# Sheet.net
KiCad netlist of a schematic drawn in Altium Designer
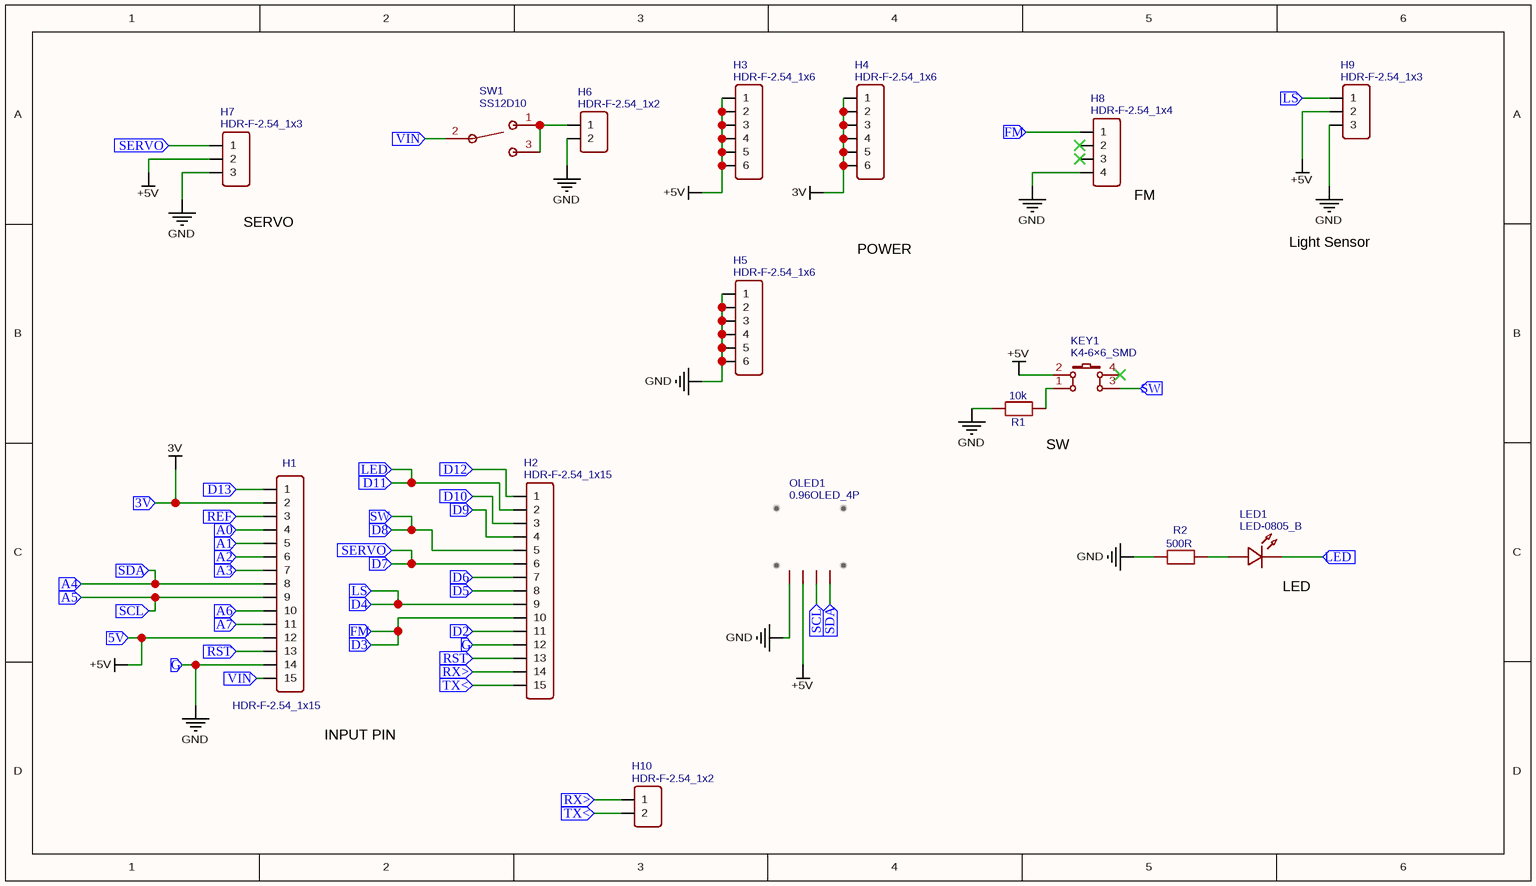
[diagram p0: Sheet.schdoc]

(export (version "E")
  (design (tool "Eeschema 10.0.6"))
  (components
    (comp (ref "H1")
      (value "HDR-F-2.54_1x15")
      (fields (field (name "BOM_SUPPLIER PART") "C124408") (field (name "CONTRIBUTOR") "LCEDA_Lib"))
      (libsource (lib "altium-import") (part "root_0_HDR-F-2.54_1x15_"))
    )
    (comp (ref "H2")
      (value "HDR-F-2.54_1x15")
      (fields (field (name "BOM_SUPPLIER PART") "C124408") (field (name "CONTRIBUTOR") "LCEDA_Lib"))
      (libsource (lib "altium-import") (part "root_0_HDR-F-2.54_1x15_"))
    )
    (comp (ref "H3")
      (value "HDR-F-2.54_1x6")
      (fields (field (name "BOM_SUPPLIER PART") "C40877") (field (name "CONTRIBUTOR") "LCEDA_Lib"))
      (libsource (lib "altium-import") (part "root_0_HDR-F-2.54_1x6_"))
    )
    (comp (ref "H4")
      (value "HDR-F-2.54_1x6")
      (fields (field (name "BOM_SUPPLIER PART") "C40877") (field (name "CONTRIBUTOR") "LCEDA_Lib"))
      (libsource (lib "altium-import") (part "root_0_HDR-F-2.54_1x6_"))
    )
    (comp (ref "H5")
      (value "HDR-F-2.54_1x6")
      (fields (field (name "BOM_SUPPLIER PART") "C40877") (field (name "CONTRIBUTOR") "LCEDA_Lib"))
      (libsource (lib "altium-import") (part "root_0_HDR-F-2.54_1x6_"))
    )
    (comp (ref "H6")
      (value "HDR-F-2.54_1x2")
      (fields (field (name "BOM_SUPPLIER PART") "C49661") (field (name "CONTRIBUTOR") "LCEDA_Lib"))
      (libsource (lib "altium-import") (part "root_0_HDR-F-2.54_1x2_"))
    )
    (comp (ref "H7")
      (value "HDR-F-2.54_1x3")
      (fields (field (name "BOM_SUPPLIER PART") "C146690") (field (name "CONTRIBUTOR") "LCEDA_Lib"))
      (libsource (lib "altium-import") (part "root_0_HDR-F-2.54_1x3_"))
    )
    (comp (ref "H8")
      (value "HDR-F-2.54_1x4")
      (fields (field (name "BOM_SUPPLIER PART") "C225501") (field (name "CONTRIBUTOR") "LCEDA_Lib"))
      (libsource (lib "altium-import") (part "root_0_HDR-F-2.54_1x4_"))
    )
    (comp (ref "H9")
      (value "HDR-F-2.54_1x3")
      (fields (field (name "BOM_SUPPLIER PART") "C146690") (field (name "CONTRIBUTOR") "LCEDA_Lib"))
      (libsource (lib "altium-import") (part "root_0_HDR-F-2.54_1x3_"))
    )
    (comp (ref "H10")
      (value "HDR-F-2.54_1x2")
      (fields (field (name "BOM_SUPPLIER PART") "C49661") (field (name "CONTRIBUTOR") "LCEDA_Lib"))
      (libsource (lib "altium-import") (part "root_0_HDR-F-2.54_1x2_"))
    )
    (comp (ref "KEY1")
      (value "K4-6×6_SMD")
      (fields
        (field (name "BOM_SUPPLIER PART") "C191626")
        (field (name "BOM_MANUFACTURER PART") "K2-6639SP-D4SC-04")
        (field (name "CONTRIBUTOR") "LCEDA_Lib")
      )
      (libsource (lib "altium-import") (part "root_0_K4-6×6_SMD_"))
    )
    (comp (ref "LED1")
      (value "LED-0805_B")
      (fields
        (field (name "BOM_MANUFACTURER PART") "D-B080508B1-KS2")
        (field (name "BOM_SUPPLIER PART") "C108412")
        (field (name "CONTRIBUTOR") "LCEDA_Lib")
      )
      (libsource (lib "altium-import") (part "root_0_LED-0805_B_"))
    )
    (comp (ref "OLED1")
      (value "0.96OLED_4P")
      (fields (field (name "CONTRIBUTOR") "LCEDA_Lib"))
      (libsource (lib "altium-import") (part "root_0_0.96OLED_4P_"))
    )
    (comp (ref "R1")
      (value "10k")
      (fields (field (name "CONTRIBUTOR") "LCEDA_Lib"))
      (libsource (lib "altium-import") (part "root_0_10k_"))
    )
    (comp (ref "R2")
      (value "500R")
      (fields (field (name "CONTRIBUTOR") "LCEDA_Lib"))
      (libsource (lib "altium-import") (part "root_0_500R_"))
    )
    (comp (ref "SW1")
      (value "SS12D10")
      (fields
        (field (name "BOM_SUPPLIER PART") "C273395")
        (field (name "BOM_MANUFACTURER PART") "EG1224")
        (field (name "CONTRIBUTOR") "LCSC")
      )
      (libsource (lib "altium-import") (part "root_0_SS12D10_"))
    )
  )
  (nets
    (net (code "1") (name "+5V") (class "Default")
      (node (ref "H1") (pin "12") (pinfunction "12_12") (pintype "passive"))
      (node (ref "H3") (pin "1") (pinfunction "1_1") (pintype "passive"))
      (node (ref "H3") (pin "2") (pinfunction "2_2") (pintype "passive"))
      (node (ref "H3") (pin "3") (pinfunction "3_3") (pintype "passive"))
      (node (ref "H3") (pin "4") (pinfunction "4_4") (pintype "passive"))
      (node (ref "H3") (pin "5") (pinfunction "5_5") (pintype "passive"))
      (node (ref "H3") (pin "6") (pinfunction "6_6") (pintype "passive"))
      (node (ref "H7") (pin "2") (pinfunction "2_2") (pintype "passive"))
      (node (ref "H9") (pin "2") (pinfunction "2_2") (pintype "passive"))
      (node (ref "KEY1") (pin "2") (pinfunction "2_2") (pintype "passive"))
      (node (ref "OLED1") (pin "2") (pinfunction "2_2") (pintype "passive"))
    )
    (net (code "2") (name "/A0") (class "Default")
      (node (ref "H1") (pin "4") (pinfunction "4_4") (pintype "passive"))
    )
    (net (code "3") (name "/A1") (class "Default")
      (node (ref "H1") (pin "5") (pinfunction "5_5") (pintype "passive"))
    )
    (net (code "4") (name "/A2") (class "Default")
      (node (ref "H1") (pin "6") (pinfunction "6_6") (pintype "passive"))
    )
    (net (code "5") (name "/A3") (class "Default")
      (node (ref "H1") (pin "7") (pinfunction "7_7") (pintype "passive"))
    )
    (net (code "6") (name "/A4") (class "Default")
      (node (ref "H1") (pin "8") (pinfunction "8_8") (pintype "passive"))
      (node (ref "OLED1") (pin "4") (pinfunction "4_4") (pintype "passive"))
    )
    (net (code "7") (name "/A5") (class "Default")
      (node (ref "H1") (pin "9") (pinfunction "9_9") (pintype "passive"))
      (node (ref "OLED1") (pin "3") (pinfunction "3_3") (pintype "passive"))
    )
    (net (code "8") (name "/A6") (class "Default")
      (node (ref "H1") (pin "10") (pinfunction "10_10") (pintype "passive"))
    )
    (net (code "9") (name "/A7") (class "Default")
      (node (ref "H1") (pin "11") (pinfunction "11_11") (pintype "passive"))
    )
    (net (code "10") (name "/D2") (class "Default")
      (node (ref "H2") (pin "11") (pinfunction "11_11") (pintype "passive"))
    )
    (net (code "11") (name "/D3") (class "Default")
      (node (ref "H2") (pin "10") (pinfunction "10_10") (pintype "passive"))
      (node (ref "H8") (pin "1") (pinfunction "1_1") (pintype "passive"))
    )
    (net (code "12") (name "/D4") (class "Default")
      (node (ref "H2") (pin "9") (pinfunction "9_9") (pintype "passive"))
      (node (ref "H9") (pin "1") (pinfunction "1_1") (pintype "passive"))
    )
    (net (code "13") (name "/D5") (class "Default")
      (node (ref "H2") (pin "8") (pinfunction "8_8") (pintype "passive"))
    )
    (net (code "14") (name "/D6") (class "Default")
      (node (ref "H2") (pin "7") (pinfunction "7_7") (pintype "passive"))
    )
    (net (code "15") (name "/D7") (class "Default")
      (node (ref "H2") (pin "6") (pinfunction "6_6") (pintype "passive"))
      (node (ref "H7") (pin "1") (pinfunction "1_1") (pintype "passive"))
    )
    (net (code "16") (name "/D8") (class "Default")
      (node (ref "H2") (pin "5") (pinfunction "5_5") (pintype "passive"))
      (node (ref "KEY1") (pin "3") (pinfunction "3_3") (pintype "passive"))
    )
    (net (code "17") (name "/D9") (class "Default")
      (node (ref "H2") (pin "4") (pinfunction "4_4") (pintype "passive"))
    )
    (net (code "18") (name "/D10") (class "Default")
      (node (ref "H2") (pin "3") (pinfunction "3_3") (pintype "passive"))
    )
    (net (code "19") (name "/D11") (class "Default")
      (node (ref "H2") (pin "2") (pinfunction "2_2") (pintype "passive"))
      (node (ref "LED1") (pin "2") (pinfunction "2_2") (pintype "passive"))
    )
    (net (code "20") (name "/D12") (class "Default")
      (node (ref "H2") (pin "1") (pinfunction "1_1") (pintype "passive"))
    )
    (net (code "21") (name "/D13") (class "Default")
      (node (ref "H1") (pin "1") (pinfunction "1_1") (pintype "passive"))
    )
    (net (code "22") (name "/REF") (class "Default")
      (node (ref "H1") (pin "3") (pinfunction "3_3") (pintype "passive"))
    )
    (net (code "23") (name "/RST") (class "Default")
      (node (ref "H1") (pin "13") (pinfunction "13_13") (pintype "passive"))
      (node (ref "H2") (pin "13") (pinfunction "13_13") (pintype "passive"))
    )
    (net (code "24") (name "/RX>") (class "Default")
      (node (ref "H10") (pin "1") (pinfunction "1_1") (pintype "passive"))
      (node (ref "H2") (pin "14") (pinfunction "14_14") (pintype "passive"))
    )
    (net (code "25") (name "/TX<") (class "Default")
      (node (ref "H10") (pin "2") (pinfunction "2_2") (pintype "passive"))
      (node (ref "H2") (pin "15") (pinfunction "15_15") (pintype "passive"))
    )
    (net (code "26") (name "/VIN") (class "Default")
      (node (ref "H1") (pin "15") (pinfunction "15_15") (pintype "passive"))
      (node (ref "SW1") (pin "2") (pinfunction "2_2") (pintype "passive"))
    )
    (net (code "27") (name "3V") (class "Default")
      (node (ref "H1") (pin "2") (pinfunction "2_2") (pintype "passive"))
      (node (ref "H4") (pin "1") (pinfunction "1_1") (pintype "passive"))
      (node (ref "H4") (pin "2") (pinfunction "2_2") (pintype "passive"))
      (node (ref "H4") (pin "3") (pinfunction "3_3") (pintype "passive"))
      (node (ref "H4") (pin "4") (pinfunction "4_4") (pintype "passive"))
      (node (ref "H4") (pin "5") (pinfunction "5_5") (pintype "passive"))
      (node (ref "H4") (pin "6") (pinfunction "6_6") (pintype "passive"))
    )
    (net (code "28") (name "GND") (class "Default")
      (node (ref "H1") (pin "14") (pinfunction "14_14") (pintype "passive"))
      (node (ref "H2") (pin "12") (pinfunction "12_12") (pintype "passive"))
      (node (ref "H5") (pin "1") (pinfunction "1_1") (pintype "passive"))
      (node (ref "H5") (pin "2") (pinfunction "2_2") (pintype "passive"))
      (node (ref "H5") (pin "3") (pinfunction "3_3") (pintype "passive"))
      (node (ref "H5") (pin "4") (pinfunction "4_4") (pintype "passive"))
      (node (ref "H5") (pin "5") (pinfunction "5_5") (pintype "passive"))
      (node (ref "H5") (pin "6") (pinfunction "6_6") (pintype "passive"))
      (node (ref "H6") (pin "2") (pinfunction "2_2") (pintype "passive"))
      (node (ref "H7") (pin "3") (pinfunction "3_3") (pintype "passive"))
      (node (ref "H8") (pin "4") (pinfunction "4_4") (pintype "passive"))
      (node (ref "H9") (pin "3") (pinfunction "3_3") (pintype "passive"))
      (node (ref "OLED1") (pin "1") (pinfunction "1_1") (pintype "passive"))
      (node (ref "R1") (pin "1") (pinfunction "1_1") (pintype "passive"))
      (node (ref "R2") (pin "1") (pinfunction "1_1") (pintype "passive"))
    )
    (net (code "29") (name "Net-(H6-Pad1)") (class "Default")
      (node (ref "H6") (pin "1") (pinfunction "1_1") (pintype "passive"))
      (node (ref "SW1") (pin "1") (pinfunction "1_1") (pintype "passive"))
      (node (ref "SW1") (pin "3") (pinfunction "3_3") (pintype "passive"))
    )
    (net (code "30") (name "Net-(KEY1-Pad1)") (class "Default")
      (node (ref "KEY1") (pin "1") (pinfunction "1_1") (pintype "passive"))
      (node (ref "R1") (pin "2") (pinfunction "2_2") (pintype "passive"))
    )
    (net (code "31") (name "Net-(LED1-Pad1)") (class "Default")
      (node (ref "LED1") (pin "1") (pinfunction "1_1") (pintype "passive"))
      (node (ref "R2") (pin "2") (pinfunction "2_2") (pintype "passive"))
    )
    (net (code "32") (name "unconnected-(H8-Pad2)") (class "Default")
      (node (ref "H8") (pin "2") (pinfunction "2_2") (pintype "passive+no_connect"))
    )
    (net (code "33") (name "unconnected-(H8-Pad3)") (class "Default")
      (node (ref "H8") (pin "3") (pinfunction "3_3") (pintype "passive+no_connect"))
    )
    (net (code "34") (name "unconnected-(KEY1-Pad4)") (class "Default")
      (node (ref "KEY1") (pin "4") (pinfunction "4_4") (pintype "passive+no_connect"))
    )
  )
)
